# shige7seg_earring.net
KiCad netlist of a schematic drawn in EAGLE
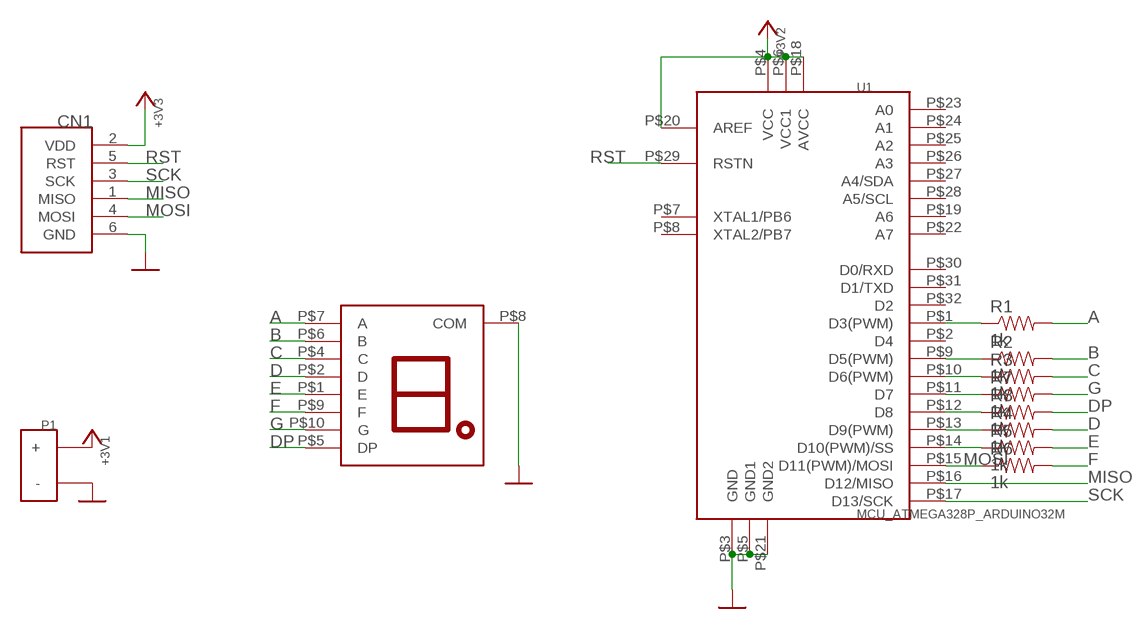
[diagram p0: schematic, sheet 1]

(export (version "E")
  (design (tool "Eeschema 10.0.6"))
  (components
    (comp (ref "CN1")
      (value "CON_AVRISPTH")
      (footprint "eagle-import:2X03R")
      (libsource (lib "eagle-import") (part "CON_AVRISPTH"))
    )
    (comp (ref "D1")
      (value "LED_7SEG")
      (footprint "eagle-import:7SEG_10X7SMD")
      (libsource (lib "eagle-import") (part "LED_7SEG"))
    )
    (comp (ref "P1")
      (value "BATTERYCOIN1220")
      (footprint "eagle-import:BAT_CR1220_SMD")
      (libsource (lib "eagle-import") (part "BATTERYCOIN1220"))
    )
    (comp (ref "R1")
      (value "1k")
      (footprint "eagle-import:0603")
      (libsource (lib "eagle-import") (part "RES0603"))
    )
    (comp (ref "R2")
      (value "1k")
      (footprint "eagle-import:0603")
      (libsource (lib "eagle-import") (part "RES0603"))
    )
    (comp (ref "R3")
      (value "1k")
      (footprint "eagle-import:0603")
      (libsource (lib "eagle-import") (part "RES0603"))
    )
    (comp (ref "R4")
      (value "1k")
      (footprint "eagle-import:0603")
      (libsource (lib "eagle-import") (part "RES0603"))
    )
    (comp (ref "R5")
      (value "1k")
      (footprint "eagle-import:0603")
      (libsource (lib "eagle-import") (part "RES0603"))
    )
    (comp (ref "R6")
      (value "1k")
      (footprint "eagle-import:0603")
      (libsource (lib "eagle-import") (part "RES0603"))
    )
    (comp (ref "R7")
      (value "1k")
      (footprint "eagle-import:0603")
      (libsource (lib "eagle-import") (part "RES0603"))
    )
    (comp (ref "R8")
      (value "1k")
      (footprint "eagle-import:0603")
      (libsource (lib "eagle-import") (part "RES0603"))
    )
    (comp (ref "U1")
      (value "MCU_ATMEGA328P_ARDUINO32M")
      (footprint "eagle-import:QFN32")
      (libsource (lib "eagle-import") (part "MCU_ATMEGA328P_ARDUINO32M"))
    )
  )
  (nets
    (net (code "1") (name "/A") (class "Default")
      (node (ref "D1") (pin "P$7") (pinfunction "A_P$7") (pintype "bidirectional"))
      (node (ref "R1") (pin "2") (pinfunction "2_2") (pintype "passive"))
    )
    (net (code "2") (name "/B") (class "Default")
      (node (ref "D1") (pin "P$6") (pinfunction "B_P$6") (pintype "bidirectional"))
      (node (ref "R2") (pin "2") (pinfunction "2_2") (pintype "passive"))
    )
    (net (code "3") (name "/C") (class "Default")
      (node (ref "D1") (pin "P$4") (pinfunction "C_P$4") (pintype "bidirectional"))
      (node (ref "R3") (pin "2") (pinfunction "2_2") (pintype "passive"))
    )
    (net (code "4") (name "/D") (class "Default")
      (node (ref "D1") (pin "P$2") (pinfunction "D_P$2") (pintype "bidirectional"))
      (node (ref "R4") (pin "2") (pinfunction "2_2") (pintype "passive"))
    )
    (net (code "5") (name "/DP") (class "Default")
      (node (ref "D1") (pin "P$5") (pinfunction "DP_P$5") (pintype "bidirectional"))
      (node (ref "R8") (pin "2") (pinfunction "2_2") (pintype "passive"))
    )
    (net (code "6") (name "/E") (class "Default")
      (node (ref "D1") (pin "P$1") (pinfunction "E_P$1") (pintype "bidirectional"))
      (node (ref "R5") (pin "2") (pinfunction "2_2") (pintype "passive"))
    )
    (net (code "7") (name "/F") (class "Default")
      (node (ref "D1") (pin "P$9") (pinfunction "F_P$9") (pintype "bidirectional"))
      (node (ref "R6") (pin "2") (pinfunction "2_2") (pintype "passive"))
    )
    (net (code "8") (name "/G") (class "Default")
      (node (ref "D1") (pin "P$10") (pinfunction "G_P$10") (pintype "bidirectional"))
      (node (ref "R7") (pin "2") (pinfunction "2_2") (pintype "passive"))
    )
    (net (code "9") (name "/MISO") (class "Default")
      (node (ref "CN1") (pin "1") (pinfunction "MISO_1") (pintype "bidirectional"))
      (node (ref "U1") (pin "P$16") (pinfunction "D12/MISO_P$16") (pintype "bidirectional"))
    )
    (net (code "10") (name "/MOSI") (class "Default")
      (node (ref "CN1") (pin "4") (pinfunction "MOSI_4") (pintype "bidirectional"))
      (node (ref "R6") (pin "1") (pinfunction "1_1") (pintype "passive"))
      (node (ref "U1") (pin "P$15") (pinfunction "D11(PWM)/MOSI_P$15") (pintype "bidirectional"))
    )
    (net (code "11") (name "/RST") (class "Default")
      (node (ref "CN1") (pin "5") (pinfunction "RST_5") (pintype "bidirectional"))
      (node (ref "U1") (pin "P$29") (pinfunction "RSTN_P$29") (pintype "bidirectional"))
    )
    (net (code "12") (name "/SCK") (class "Default")
      (node (ref "CN1") (pin "3") (pinfunction "SCK_3") (pintype "bidirectional"))
      (node (ref "U1") (pin "P$17") (pinfunction "D13/SCK_P$17") (pintype "bidirectional"))
    )
    (net (code "13") (name "Net-(U1-D3(PWM))") (class "Default")
      (node (ref "R1") (pin "1") (pinfunction "1_1") (pintype "passive"))
      (node (ref "U1") (pin "P$1") (pinfunction "D3(PWM)_P$1") (pintype "bidirectional"))
    )
    (net (code "14") (name "Net-(U1-D5(PWM))") (class "Default")
      (node (ref "R2") (pin "1") (pinfunction "1_1") (pintype "passive"))
      (node (ref "U1") (pin "P$9") (pinfunction "D5(PWM)_P$9") (pintype "bidirectional"))
    )
    (net (code "15") (name "Net-(U1-D6(PWM))") (class "Default")
      (node (ref "R3") (pin "1") (pinfunction "1_1") (pintype "passive"))
      (node (ref "U1") (pin "P$10") (pinfunction "D6(PWM)_P$10") (pintype "bidirectional"))
    )
    (net (code "16") (name "Net-(U1-D7)") (class "Default")
      (node (ref "R7") (pin "1") (pinfunction "1_1") (pintype "passive"))
      (node (ref "U1") (pin "P$11") (pinfunction "D7_P$11") (pintype "bidirectional"))
    )
    (net (code "17") (name "Net-(U1-D8)") (class "Default")
      (node (ref "R8") (pin "1") (pinfunction "1_1") (pintype "passive"))
      (node (ref "U1") (pin "P$12") (pinfunction "D8_P$12") (pintype "bidirectional"))
    )
    (net (code "18") (name "Net-(U1-D9(PWM))") (class "Default")
      (node (ref "R4") (pin "1") (pinfunction "1_1") (pintype "passive"))
      (node (ref "U1") (pin "P$13") (pinfunction "D9(PWM)_P$13") (pintype "bidirectional"))
    )
    (net (code "19") (name "Net-(U1-D10(PWM){slash}SS)") (class "Default")
      (node (ref "R5") (pin "1") (pinfunction "1_1") (pintype "passive"))
      (node (ref "U1") (pin "P$14") (pinfunction "D10(PWM)/SS_P$14") (pintype "bidirectional"))
    )
    (net (code "20") (name "POW_+3V3") (class "Default")
      (node (ref "CN1") (pin "2") (pinfunction "VDD_2") (pintype "bidirectional"))
      (node (ref "P1") (pin "P") (pinfunction "+_P") (pintype "power_in"))
      (node (ref "U1") (pin "P$18") (pinfunction "AVCC_P$18") (pintype "power_in"))
      (node (ref "U1") (pin "P$20") (pinfunction "AREF_P$20") (pintype "bidirectional"))
      (node (ref "U1") (pin "P$4") (pinfunction "VCC_P$4") (pintype "power_in"))
      (node (ref "U1") (pin "P$6") (pinfunction "VCC1_P$6") (pintype "power_in"))
    )
    (net (code "21") (name "POW_GND") (class "Default")
      (node (ref "CN1") (pin "6") (pinfunction "GND_6") (pintype "bidirectional"))
      (node (ref "D1") (pin "P$8") (pinfunction "COM_P$8") (pintype "bidirectional"))
      (node (ref "P1") (pin "M") (pinfunction "-_M") (pintype "power_in"))
      (node (ref "U1") (pin "P$21") (pinfunction "GND2_P$21") (pintype "power_in"))
      (node (ref "U1") (pin "P$3") (pinfunction "GND_P$3") (pintype "power_in"))
      (node (ref "U1") (pin "P$5") (pinfunction "GND1_P$5") (pintype "power_in"))
    )
    (net (code "22") (name "unconnected-(U1-A0-PadP$23)") (class "Default")
      (node (ref "U1") (pin "P$23") (pinfunction "A0_P$23") (pintype "bidirectional"))
    )
    (net (code "23") (name "unconnected-(U1-A1-PadP$24)") (class "Default")
      (node (ref "U1") (pin "P$24") (pinfunction "A1_P$24") (pintype "bidirectional"))
    )
    (net (code "24") (name "unconnected-(U1-A2-PadP$25)") (class "Default")
      (node (ref "U1") (pin "P$25") (pinfunction "A2_P$25") (pintype "bidirectional"))
    )
    (net (code "25") (name "unconnected-(U1-A3-PadP$26)") (class "Default")
      (node (ref "U1") (pin "P$26") (pinfunction "A3_P$26") (pintype "bidirectional"))
    )
    (net (code "26") (name "unconnected-(U1-A4{slash}SDA-PadP$27)") (class "Default")
      (node (ref "U1") (pin "P$27") (pinfunction "A4/SDA_P$27") (pintype "bidirectional"))
    )
    (net (code "27") (name "unconnected-(U1-A5{slash}SCL-PadP$28)") (class "Default")
      (node (ref "U1") (pin "P$28") (pinfunction "A5/SCL_P$28") (pintype "bidirectional"))
    )
    (net (code "28") (name "unconnected-(U1-A6-PadP$19)") (class "Default")
      (node (ref "U1") (pin "P$19") (pinfunction "A6_P$19") (pintype "bidirectional"))
    )
    (net (code "29") (name "unconnected-(U1-A7-PadP$22)") (class "Default")
      (node (ref "U1") (pin "P$22") (pinfunction "A7_P$22") (pintype "bidirectional"))
    )
    (net (code "30") (name "unconnected-(U1-D0{slash}RXD-PadP$30)") (class "Default")
      (node (ref "U1") (pin "P$30") (pinfunction "D0/RXD_P$30") (pintype "bidirectional"))
    )
    (net (code "31") (name "unconnected-(U1-D1{slash}TXD-PadP$31)") (class "Default")
      (node (ref "U1") (pin "P$31") (pinfunction "D1/TXD_P$31") (pintype "bidirectional"))
    )
    (net (code "32") (name "unconnected-(U1-D2-PadP$32)") (class "Default")
      (node (ref "U1") (pin "P$32") (pinfunction "D2_P$32") (pintype "bidirectional"))
    )
    (net (code "33") (name "unconnected-(U1-D4-PadP$2)") (class "Default")
      (node (ref "U1") (pin "P$2") (pinfunction "D4_P$2") (pintype "bidirectional"))
    )
    (net (code "34") (name "unconnected-(U1-XTAL1{slash}PB6-PadP$7)") (class "Default")
      (node (ref "U1") (pin "P$7") (pinfunction "XTAL1/PB6_P$7") (pintype "bidirectional"))
    )
    (net (code "35") (name "unconnected-(U1-XTAL2{slash}PB7-PadP$8)") (class "Default")
      (node (ref "U1") (pin "P$8") (pinfunction "XTAL2/PB7_P$8") (pintype "bidirectional"))
    )
  )
)
